# 2_ESP32_SoC_schdoc.net
KiCad netlist of a schematic drawn in Altium Designer
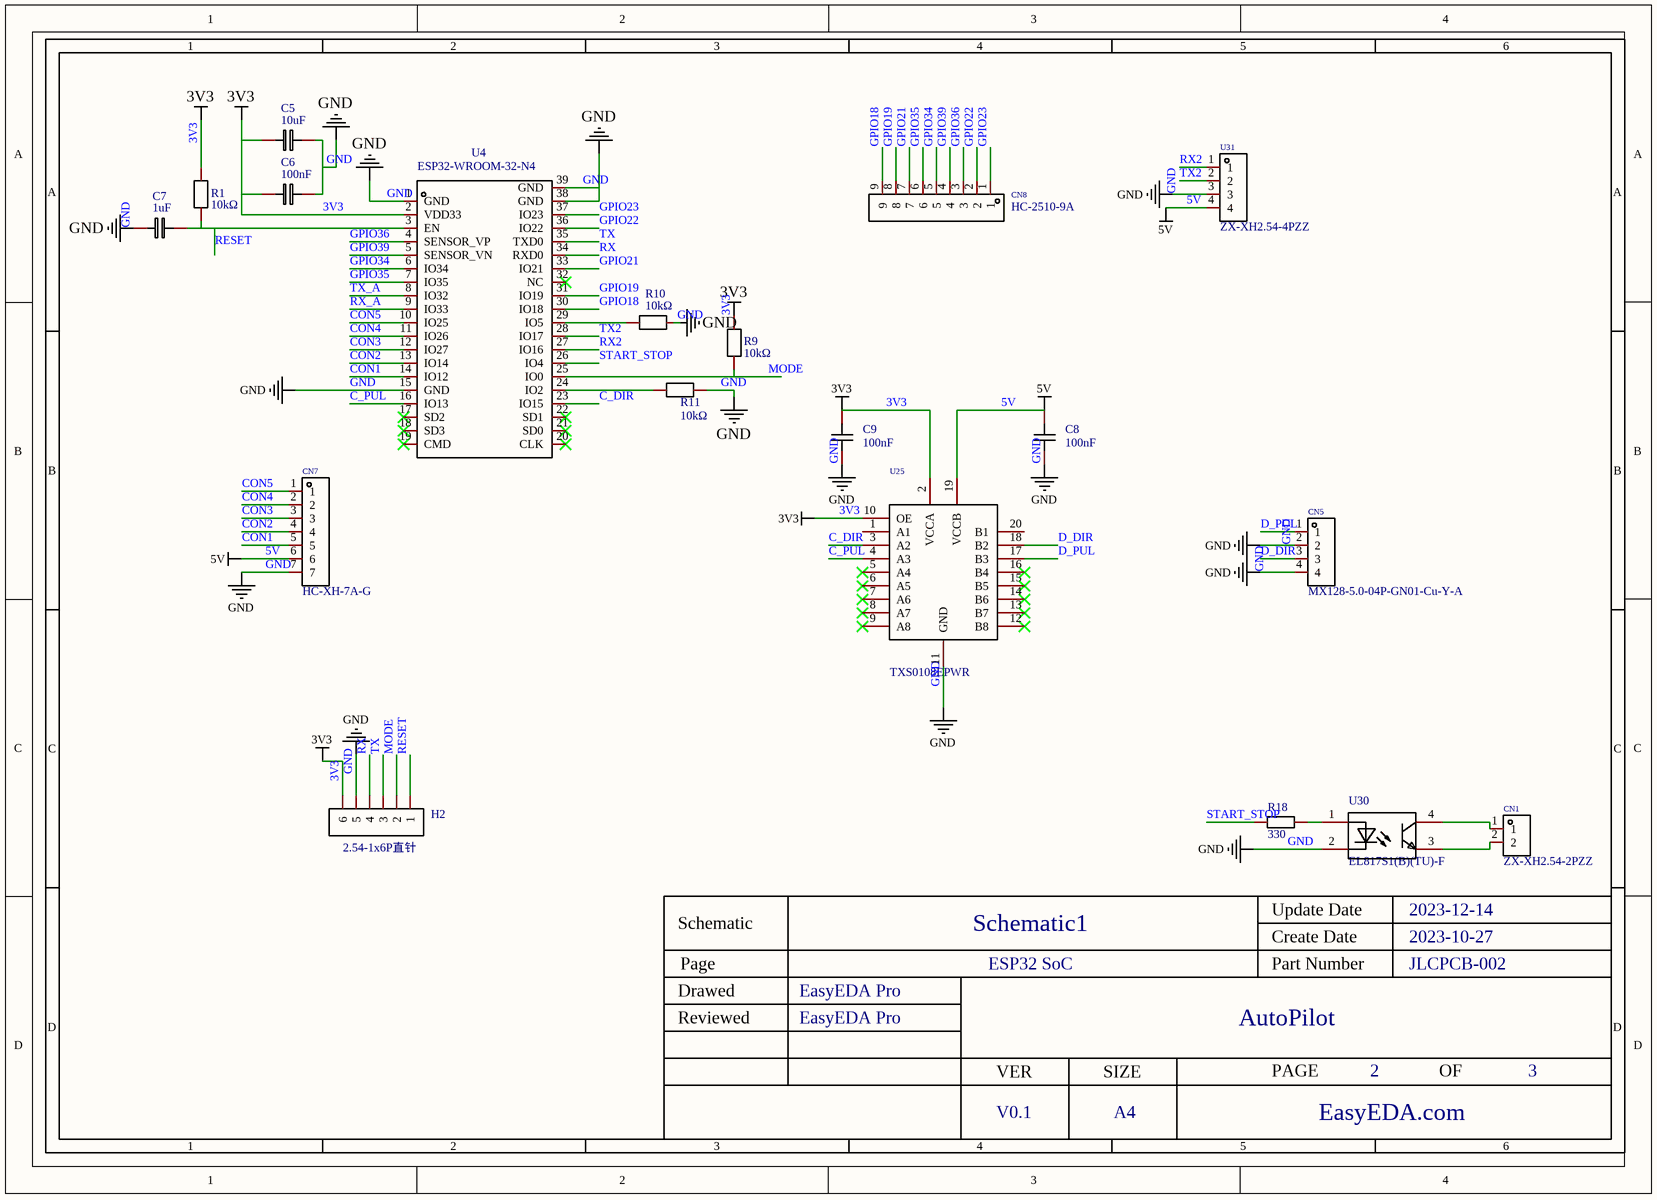
[diagram p0: 2_ESP32 SoC.schdoc.schdoc]

(export (version "E")
  (design (tool "Eeschema 10.0.6"))
  (components
    (comp (ref "C5")
      (value "10uF")
      (fields
        (field (name "NAME") "10uF")
        (field (name "MANUFACTURER") "SAMSUNG(三星)")
        (field (name "MANUFACTURER PART") "CL10A106MQ8NNNC")
        (field (name "TOLERANCE") "±20%")
      )
      (libsource (lib "altium-import") (part "root_0_CL10A106MQ8NNNC_"))
    )
    (comp (ref "C6")
      (value "100nF")
      (fields
        (field (name "NAME") "100nF")
        (field (name "MANUFACTURER PART") "C0603C104K5RACAUTO")
        (field (name "MANUFACTURER") "KEMET(基美)")
      )
      (libsource (lib "altium-import") (part "root_0_0.1u_"))
    )
    (comp (ref "C7")
      (value "1uF")
      (fields
        (field (name "NAME") "1uF")
        (field (name "MANUFACTURER PART") "CC0603ZRY5V8BB105")
        (field (name "MANUFACTURER") "YAGEO(国巨)")
      )
      (libsource (lib "altium-import") (part "root_0_1u_"))
    )
    (comp (ref "C8")
      (value "100nF")
      (fields (field (name "NAME") "100nF"))
      (libsource (lib "altium-import") (part "root_1_CAP_0603_"))
    )
    (comp (ref "C9")
      (value "100nF")
      (fields (field (name "NAME") "100nF"))
      (libsource (lib "altium-import") (part "root_1_CAP_0603_"))
    )
    (comp (ref "CN1")
      (value "ZX-XH2.54-2PZZ")
      (fields (field (name "NAME") "ZX-XH2.54-2PZZ") (field (name "MANUFACTURER") "Megastar(兆星)"))
      (libsource (lib "altium-import") (part "root_0_ZX-XH2.54-2PZZ_"))
    )
    (comp (ref "CN5")
      (value "MX128-5.0-04P-GN01-Cu-Y-A")
      (fields (field (name "NAME") "MX128-5.0-04P-GN01-Cu-Y-A") (field (name "MANUFACTURER") "MAX(迈旭)"))
      (libsource (lib "altium-import") (part "root_0_MX128-5.0-04P-GN01-Cu-Y-A_"))
    )
    (comp (ref "CN7")
      (value "HC-XH-7A-G")
      (fields (field (name "NAME") "HC-XH-7A-G") (field (name "MANUFACTURER") "HCTL(华灿天禄)"))
      (libsource (lib "altium-import") (part "root_0_HC-XH-7A-G_"))
    )
    (comp (ref "CN8")
      (value "HC-2510-9A")
      (fields (field (name "NAME") "HC-2510-9A") (field (name "MANUFACTURER") "HCTL(华灿天禄)"))
      (libsource (lib "altium-import") (part "root_3_HC-2510-9A_"))
    )
    (comp (ref "H2")
      (value "2.54-1x6P直针")
      (fields (field (name "NAME") "2.54-1x6P直针") (field (name "MANUFACTURER") "BOOMELE(博穆精密)"))
      (libsource (lib "altium-import") (part "root_3_2.54-1x6P直针_"))
    )
    (comp (ref "R1")
      (value "10kΩ")
      (description "Resistance: Tolerance:±1% Tolerance:±1%")
      (fields
        (field (name "NAME") "10kΩ")
        (field (name "MANUFACTURER") "VO(翔胜)")
        (field (name "MANUFACTURER PART") "SCR0402F10K")
      )
      (libsource (lib "altium-import") (part "root_1_SCR0402F10K_"))
    )
    (comp (ref "R9")
      (value "10kΩ")
      (description "Resistance: Tolerance:±1% Tolerance:±1%")
      (fields
        (field (name "NAME") "10kΩ")
        (field (name "MANUFACTURER") "VO(翔胜)")
        (field (name "MANUFACTURER PART") "SCR0402F10K")
      )
      (libsource (lib "altium-import") (part "root_1_SCR0402F10K_"))
    )
    (comp (ref "R10")
      (value "10kΩ")
      (description "Resistance: Tolerance:±1% Tolerance:±1%")
      (fields
        (field (name "NAME") "10kΩ")
        (field (name "MANUFACTURER") "VO(翔胜)")
        (field (name "MANUFACTURER PART") "SCR0402F10K")
      )
      (libsource (lib "altium-import") (part "root_0_SCR0402F10K_"))
    )
    (comp (ref "R11")
      (value "10kΩ")
      (description "Resistance: Tolerance:±1% Tolerance:±1%")
      (fields
        (field (name "NAME") "10kΩ")
        (field (name "MANUFACTURER") "VO(翔胜)")
        (field (name "MANUFACTURER PART") "SCR0402F10K")
      )
      (libsource (lib "altium-import") (part "root_0_SCR0402F10K_"))
    )
    (comp (ref "R18")
      (value "330")
      (fields (field (name "NAME") "330"))
      (libsource (lib "altium-import") (part "root_0_Res_0603_"))
    )
    (comp (ref "U4")
      (value "ESP32-WROOM-32-N4")
      (fields (field (name "NAME") "ESP32-WROOM-32-N4") (field (name "MANUFACTURER") "ESPRESSIF(乐鑫)"))
      (libsource (lib "altium-import") (part "root_0_ESP32-WROOM-32-N4_"))
    )
    (comp (ref "U25")
      (value "TXS0108EPWR")
      (fields (field (name "NAME") "TXS0108EPWR") (field (name "MANUFACTURER") "TI(德州仪器)"))
      (libsource (lib "altium-import") (part "root_0_TXS0108EPWR_"))
    )
    (comp (ref "U30")
      (value "EL817S1(B)(TU)-F")
      (fields (field (name "NAME") "EL817S1(B)(TU)-F") (field (name "MANUFACTURER") "EVERLIGHT(亿光)"))
      (libsource (lib "altium-import") (part "root_0_EL817S1(B)(TU)-F_"))
    )
    (comp (ref "U31")
      (value "ZX-XH2.54-4PZZ")
      (fields (field (name "NAME") "ZX-XH2.54-4PZZ") (field (name "MANUFACTURER") "Megastar(兆星)"))
      (libsource (lib "altium-import") (part "root_0_ZX-XH2.54-4PZZ_"))
    )
  )
  (nets
    (net (code "1") (name "/CON1") (class "Default")
      (node (ref "CN7") (pin "5") (pinfunction "5_5") (pintype "passive"))
      (node (ref "U4") (pin "14") (pinfunction "IO12_14") (pintype "passive"))
    )
    (net (code "2") (name "/CON2") (class "Default")
      (node (ref "CN7") (pin "4") (pinfunction "4_4") (pintype "passive"))
      (node (ref "U4") (pin "13") (pinfunction "IO14_13") (pintype "passive"))
    )
    (net (code "3") (name "/CON3") (class "Default")
      (node (ref "CN7") (pin "3") (pinfunction "3_3") (pintype "passive"))
      (node (ref "U4") (pin "12") (pinfunction "IO27_12") (pintype "passive"))
    )
    (net (code "4") (name "/CON4") (class "Default")
      (node (ref "CN7") (pin "2") (pinfunction "2_2") (pintype "passive"))
      (node (ref "U4") (pin "11") (pinfunction "IO26_11") (pintype "passive"))
    )
    (net (code "5") (name "/CON5") (class "Default")
      (node (ref "CN7") (pin "1") (pinfunction "1_1") (pintype "passive"))
      (node (ref "U4") (pin "10") (pinfunction "IO25_10") (pintype "passive"))
    )
    (net (code "6") (name "/C_DIR") (class "Default")
      (node (ref "U25") (pin "3") (pinfunction "A2_3") (pintype "passive"))
      (node (ref "U4") (pin "23") (pinfunction "IO15_23") (pintype "passive"))
    )
    (net (code "7") (name "/C_PUL") (class "Default")
      (node (ref "U25") (pin "4") (pinfunction "A3_4") (pintype "passive"))
      (node (ref "U4") (pin "16") (pinfunction "IO13_16") (pintype "passive"))
    )
    (net (code "8") (name "/D_DIR") (class "Default")
      (node (ref "CN5") (pin "3") (pinfunction "3_3") (pintype "passive"))
      (node (ref "U25") (pin "18") (pinfunction "B2_18") (pintype "passive"))
    )
    (net (code "9") (name "/D_PUL") (class "Default")
      (node (ref "CN5") (pin "1") (pinfunction "1_1") (pintype "passive"))
      (node (ref "U25") (pin "17") (pinfunction "B3_17") (pintype "passive"))
    )
    (net (code "10") (name "/GPIO18") (class "Default")
      (node (ref "CN8") (pin "9") (pinfunction "9_9") (pintype "passive"))
      (node (ref "U4") (pin "30") (pinfunction "IO18_30") (pintype "passive"))
    )
    (net (code "11") (name "/GPIO19") (class "Default")
      (node (ref "CN8") (pin "8") (pinfunction "8_8") (pintype "passive"))
      (node (ref "U4") (pin "31") (pinfunction "IO19_31") (pintype "passive"))
    )
    (net (code "12") (name "/GPIO21") (class "Default")
      (node (ref "CN8") (pin "7") (pinfunction "7_7") (pintype "passive"))
      (node (ref "U4") (pin "33") (pinfunction "IO21_33") (pintype "passive"))
    )
    (net (code "13") (name "/GPIO22") (class "Default")
      (node (ref "CN8") (pin "2") (pinfunction "2_2") (pintype "passive"))
      (node (ref "U4") (pin "36") (pinfunction "IO22_36") (pintype "passive"))
    )
    (net (code "14") (name "/GPIO23") (class "Default")
      (node (ref "CN8") (pin "1") (pinfunction "1_1") (pintype "passive"))
      (node (ref "U4") (pin "37") (pinfunction "IO23_37") (pintype "passive"))
    )
    (net (code "15") (name "/GPIO34") (class "Default")
      (node (ref "CN8") (pin "5") (pinfunction "5_5") (pintype "passive"))
      (node (ref "U4") (pin "6") (pinfunction "IO34_6") (pintype "passive"))
    )
    (net (code "16") (name "/GPIO35") (class "Default")
      (node (ref "CN8") (pin "6") (pinfunction "6_6") (pintype "passive"))
      (node (ref "U4") (pin "7") (pinfunction "IO35_7") (pintype "passive"))
    )
    (net (code "17") (name "/GPIO36") (class "Default")
      (node (ref "CN8") (pin "3") (pinfunction "3_3") (pintype "passive"))
      (node (ref "U4") (pin "4") (pinfunction "SENSOR_VP_4") (pintype "passive"))
    )
    (net (code "18") (name "/GPIO39") (class "Default")
      (node (ref "CN8") (pin "4") (pinfunction "4_4") (pintype "passive"))
      (node (ref "U4") (pin "5") (pinfunction "SENSOR_VN_5") (pintype "passive"))
    )
    (net (code "19") (name "/MODE") (class "Default")
      (node (ref "H2") (pin "2") (pinfunction "2_2") (pintype "passive"))
      (node (ref "R9") (pin "1") (pinfunction "1_1") (pintype "passive"))
      (node (ref "U4") (pin "25") (pinfunction "IO0_25") (pintype "passive"))
    )
    (net (code "20") (name "/RESET") (class "Default")
      (node (ref "C7") (pin "2") (pinfunction "2_2") (pintype "passive"))
      (node (ref "H2") (pin "1") (pinfunction "1_1") (pintype "passive"))
      (node (ref "R1") (pin "1") (pinfunction "1_1") (pintype "passive"))
      (node (ref "U4") (pin "3") (pinfunction "EN_3") (pintype "passive"))
    )
    (net (code "21") (name "/RX") (class "Default")
      (node (ref "H2") (pin "4") (pinfunction "4_4") (pintype "passive"))
      (node (ref "U4") (pin "34") (pinfunction "RXD0_34") (pintype "passive"))
    )
    (net (code "22") (name "/RX2") (class "Default")
      (node (ref "U31") (pin "1") (pinfunction "1_1") (pintype "passive"))
      (node (ref "U4") (pin "27") (pinfunction "IO16_27") (pintype "passive"))
    )
    (net (code "23") (name "/RX_A") (class "Default")
      (node (ref "U4") (pin "9") (pinfunction "IO33_9") (pintype "passive"))
    )
    (net (code "24") (name "/START_STOP") (class "Default")
      (node (ref "R18") (pin "1") (pinfunction "1_1") (pintype "passive"))
      (node (ref "U4") (pin "26") (pinfunction "IO4_26") (pintype "passive"))
    )
    (net (code "25") (name "/TX") (class "Default")
      (node (ref "H2") (pin "3") (pinfunction "3_3") (pintype "passive"))
      (node (ref "U4") (pin "35") (pinfunction "TXD0_35") (pintype "passive"))
    )
    (net (code "26") (name "/TX2") (class "Default")
      (node (ref "U31") (pin "2") (pinfunction "2_2") (pintype "passive"))
      (node (ref "U4") (pin "28") (pinfunction "IO17_28") (pintype "passive"))
    )
    (net (code "27") (name "/TX_A") (class "Default")
      (node (ref "U4") (pin "8") (pinfunction "IO32_8") (pintype "passive"))
    )
    (net (code "28") (name "3V3") (class "Default")
      (node (ref "C5") (pin "1") (pinfunction "1_1") (pintype "passive"))
      (node (ref "C6") (pin "1") (pinfunction "1_1") (pintype "passive"))
      (node (ref "C9") (pin "1") (pinfunction "1_1") (pintype "passive"))
      (node (ref "H2") (pin "6") (pinfunction "6_6") (pintype "passive"))
      (node (ref "R1") (pin "2") (pinfunction "2_2") (pintype "passive"))
      (node (ref "R9") (pin "2") (pinfunction "2_2") (pintype "passive"))
      (node (ref "U25") (pin "10") (pinfunction "OE_10") (pintype "passive"))
      (node (ref "U25") (pin "2") (pinfunction "VCCA_2") (pintype "passive"))
      (node (ref "U4") (pin "2") (pinfunction "VDD33_2") (pintype "passive"))
    )
    (net (code "29") (name "5V") (class "Default")
      (node (ref "C8") (pin "1") (pinfunction "1_1") (pintype "passive"))
      (node (ref "CN7") (pin "6") (pinfunction "6_6") (pintype "passive"))
      (node (ref "U25") (pin "19") (pinfunction "VCCB_19") (pintype "passive"))
      (node (ref "U31") (pin "4") (pinfunction "4_4") (pintype "passive"))
    )
    (net (code "30") (name "GND") (class "Default")
      (node (ref "C5") (pin "2") (pinfunction "2_2") (pintype "passive"))
      (node (ref "C6") (pin "2") (pinfunction "2_2") (pintype "passive"))
      (node (ref "C7") (pin "1") (pinfunction "1_1") (pintype "passive"))
      (node (ref "C8") (pin "2") (pinfunction "2_2") (pintype "passive"))
      (node (ref "C9") (pin "2") (pinfunction "2_2") (pintype "passive"))
      (node (ref "CN5") (pin "2") (pinfunction "2_2") (pintype "passive"))
      (node (ref "CN5") (pin "4") (pinfunction "4_4") (pintype "passive"))
      (node (ref "CN7") (pin "7") (pinfunction "7_7") (pintype "passive"))
      (node (ref "H2") (pin "5") (pinfunction "5_5") (pintype "passive"))
      (node (ref "R10") (pin "2") (pinfunction "2_2") (pintype "passive"))
      (node (ref "R11") (pin "2") (pinfunction "2_2") (pintype "passive"))
      (node (ref "U25") (pin "11") (pinfunction "GND_11") (pintype "passive"))
      (node (ref "U30") (pin "2") (pinfunction "CAT_2") (pintype "passive"))
      (node (ref "U31") (pin "3") (pinfunction "3_3") (pintype "passive"))
      (node (ref "U4") (pin "1") (pinfunction "GND_1") (pintype "passive"))
      (node (ref "U4") (pin "15") (pinfunction "GND_15") (pintype "passive"))
      (node (ref "U4") (pin "38") (pinfunction "GND_38") (pintype "passive"))
      (node (ref "U4") (pin "39") (pinfunction "GND_39") (pintype "passive"))
    )
    (net (code "31") (name "Net-(U4-IO2)") (class "Default")
      (node (ref "R11") (pin "1") (pinfunction "1_1") (pintype "passive"))
      (node (ref "U4") (pin "24") (pinfunction "IO2_24") (pintype "passive"))
    )
    (net (code "32") (name "Net-(U4-IO5)") (class "Default")
      (node (ref "R10") (pin "1") (pinfunction "1_1") (pintype "passive"))
      (node (ref "U4") (pin "29") (pinfunction "IO5_29") (pintype "passive"))
    )
    (net (code "33") (name "Net-(U30-AN)") (class "Default")
      (node (ref "R18") (pin "2") (pinfunction "2_2") (pintype "passive"))
      (node (ref "U30") (pin "1") (pinfunction "AN_1") (pintype "passive"))
    )
    (net (code "34") (name "Net-(U30-COL)") (class "Default")
      (node (ref "CN1") (pin "1") (pinfunction "1_1") (pintype "passive"))
      (node (ref "U30") (pin "4") (pinfunction "COL_4") (pintype "passive"))
    )
    (net (code "35") (name "Net-(U30-EM)") (class "Default")
      (node (ref "CN1") (pin "2") (pinfunction "2_2") (pintype "passive"))
      (node (ref "U30") (pin "3") (pinfunction "EM_3") (pintype "passive"))
    )
    (net (code "36") (name "unconnected-(U4-CLK-Pad20)") (class "Default")
      (node (ref "U4") (pin "20") (pinfunction "CLK_20") (pintype "passive+no_connect"))
    )
    (net (code "37") (name "unconnected-(U4-CMD-Pad19)") (class "Default")
      (node (ref "U4") (pin "19") (pinfunction "CMD_19") (pintype "passive+no_connect"))
    )
    (net (code "38") (name "unconnected-(U4-NC-Pad32)") (class "Default")
      (node (ref "U4") (pin "32") (pinfunction "NC_32") (pintype "passive+no_connect"))
    )
    (net (code "39") (name "unconnected-(U4-SD0-Pad21)") (class "Default")
      (node (ref "U4") (pin "21") (pinfunction "SD0_21") (pintype "passive+no_connect"))
    )
    (net (code "40") (name "unconnected-(U4-SD1-Pad22)") (class "Default")
      (node (ref "U4") (pin "22") (pinfunction "SD1_22") (pintype "passive+no_connect"))
    )
    (net (code "41") (name "unconnected-(U4-SD2-Pad17)") (class "Default")
      (node (ref "U4") (pin "17") (pinfunction "SD2_17") (pintype "passive+no_connect"))
    )
    (net (code "42") (name "unconnected-(U4-SD3-Pad18)") (class "Default")
      (node (ref "U4") (pin "18") (pinfunction "SD3_18") (pintype "passive+no_connect"))
    )
    (net (code "43") (name "unconnected-(U25-A1-Pad1)") (class "Default")
      (node (ref "U25") (pin "1") (pinfunction "A1_1") (pintype "passive"))
    )
    (net (code "44") (name "unconnected-(U25-A4-Pad5)") (class "Default")
      (node (ref "U25") (pin "5") (pinfunction "A4_5") (pintype "passive+no_connect"))
    )
    (net (code "45") (name "unconnected-(U25-A5-Pad6)") (class "Default")
      (node (ref "U25") (pin "6") (pinfunction "A5_6") (pintype "passive+no_connect"))
    )
    (net (code "46") (name "unconnected-(U25-A6-Pad7)") (class "Default")
      (node (ref "U25") (pin "7") (pinfunction "A6_7") (pintype "passive+no_connect"))
    )
    (net (code "47") (name "unconnected-(U25-A7-Pad8)") (class "Default")
      (node (ref "U25") (pin "8") (pinfunction "A7_8") (pintype "passive+no_connect"))
    )
    (net (code "48") (name "unconnected-(U25-A8-Pad9)") (class "Default")
      (node (ref "U25") (pin "9") (pinfunction "A8_9") (pintype "passive+no_connect"))
    )
    (net (code "49") (name "unconnected-(U25-B1-Pad20)") (class "Default")
      (node (ref "U25") (pin "20") (pinfunction "B1_20") (pintype "passive"))
    )
    (net (code "50") (name "unconnected-(U25-B4-Pad16)") (class "Default")
      (node (ref "U25") (pin "16") (pinfunction "B4_16") (pintype "passive+no_connect"))
    )
    (net (code "51") (name "unconnected-(U25-B5-Pad15)") (class "Default")
      (node (ref "U25") (pin "15") (pinfunction "B5_15") (pintype "passive+no_connect"))
    )
    (net (code "52") (name "unconnected-(U25-B6-Pad14)") (class "Default")
      (node (ref "U25") (pin "14") (pinfunction "B6_14") (pintype "passive+no_connect"))
    )
    (net (code "53") (name "unconnected-(U25-B7-Pad13)") (class "Default")
      (node (ref "U25") (pin "13") (pinfunction "B7_13") (pintype "passive+no_connect"))
    )
    (net (code "54") (name "unconnected-(U25-B8-Pad12)") (class "Default")
      (node (ref "U25") (pin "12") (pinfunction "B8_12") (pintype "passive+no_connect"))
    )
  )
)
